# Cameras.net
KiCad netlist of a schematic drawn in Altium Designer
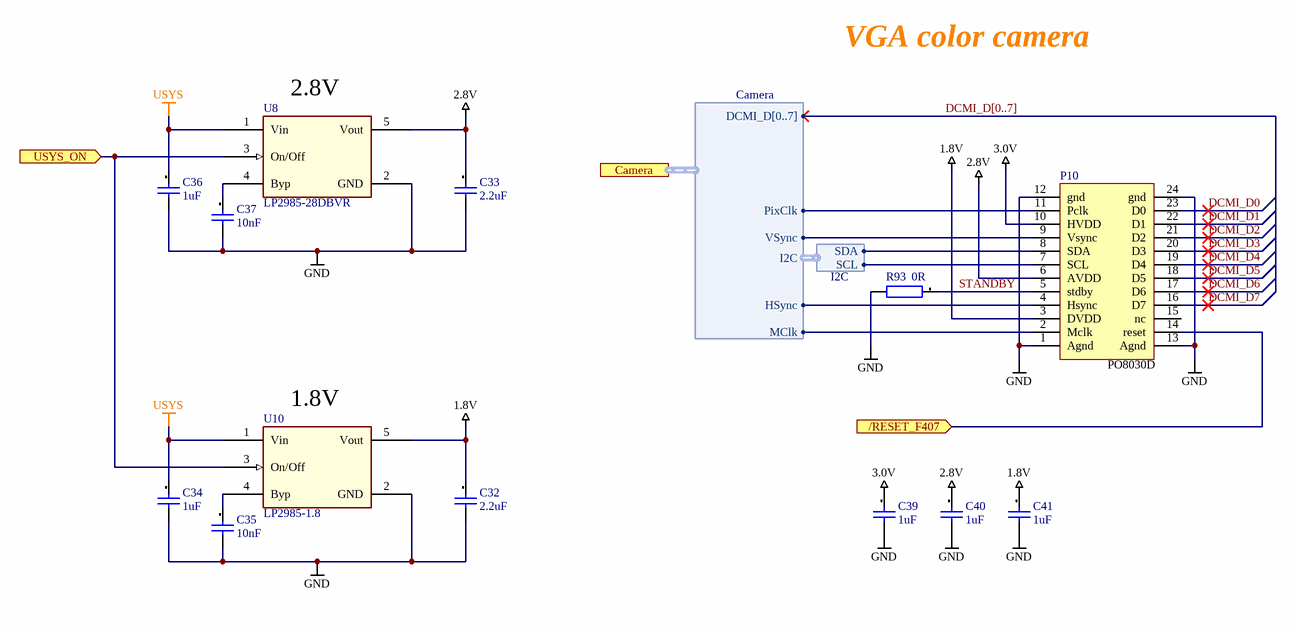
[diagram p0: Cameras.SchDoc]

(export (version "E")
  (design (tool "Eeschema 10.0.6"))
  (components
    (comp (ref "C32")
      (value "2.2uF")
      (footprint "ROB_0603")
      (description "Capacitor")
      (fields (field (name "MANUFACTURER") "Kemet") (field (name "VOLTAGE") "10"))
      (libsource (lib "LSRO1Altium") (part "CAP-NP"))
    )
    (comp (ref "C33")
      (value "2.2uF")
      (footprint "ROB_0603")
      (description "Capacitor")
      (fields (field (name "MANUFACTURER") "Kemet") (field (name "VOLTAGE") "10"))
      (libsource (lib "LSRO1Altium") (part "CAP-NP"))
    )
    (comp (ref "C34")
      (value "1uF")
      (footprint "ROB_0603")
      (description "Capacitor")
      (fields (field (name "MANUFACTURER") "Kemet") (field (name "VOLTAGE") "25"))
      (libsource (lib "LSRO1Altium") (part "CAP-NP"))
    )
    (comp (ref "C35")
      (value "10nF")
      (footprint "ROB_0603")
      (description "Capacitor")
      (fields (field (name "MANUFACTURER") "Multicomp") (field (name "VOLTAGE") "50"))
      (libsource (lib "LSRO1Altium") (part "CAP-NP"))
    )
    (comp (ref "C36")
      (value "1uF")
      (footprint "ROB_0603")
      (description "Capacitor")
      (fields (field (name "MANUFACTURER") "Kemet") (field (name "VOLTAGE") "25"))
      (libsource (lib "LSRO1Altium") (part "CAP-NP"))
    )
    (comp (ref "C37")
      (value "10nF")
      (footprint "ROB_0603")
      (description "Capacitor")
      (fields (field (name "MANUFACTURER") "Multicomp") (field (name "VOLTAGE") "50"))
      (libsource (lib "LSRO1Altium") (part "CAP-NP"))
    )
    (comp (ref "C39")
      (value "1uF")
      (footprint "ROB_0603")
      (description "Capacitor")
      (fields (field (name "MANUFACTURER") "Kemet") (field (name "VOLTAGE") "25"))
      (libsource (lib "LSRO1Altium") (part "CAP-NP"))
    )
    (comp (ref "C40")
      (value "1uF")
      (footprint "ROB_0603")
      (description "Capacitor")
      (fields (field (name "MANUFACTURER") "Kemet") (field (name "VOLTAGE") "25"))
      (libsource (lib "LSRO1Altium") (part "CAP-NP"))
    )
    (comp (ref "C41")
      (value "1uF")
      (footprint "ROB_0603")
      (description "Capacitor")
      (fields (field (name "MANUFACTURER") "Kemet") (field (name "VOLTAGE") "25"))
      (libsource (lib "LSRO1Altium") (part "CAP-NP"))
    )
    (comp (ref "P10")
      (value "24-5805-024-000-829")
      (footprint "Connector 24-5805-024-000-829")
      (description "RCPT 24 pins camera 24-5805-024-000-829")
      (libsource (lib "Dev_Card_Lib") (part "24-5805-024-000-829"))
    )
    (comp (ref "R93")
      (value "0R")
      (footprint "ROB_0603")
      (description "Resistor")
      (fields (field (name "TOLERANCE") "+/-1") (field (name "MANUFACTURER") "Multicomp"))
      (libsource (lib "LSRO1Altium") (part "RES"))
    )
    (comp (ref "U8")
      (value "LP2985-28DBVR")
      (footprint "SOT95P285X100-5L")
      (description "IC REG LDO 2.8V 0.15A SOT23-5")
      (fields (field (name "MANUFACTURER") "Texas Instruments") (field (name "Comment") "LDO 2V8"))
      (libsource (lib "Dev_Card_Lib") (part "LP2985-28DBVR"))
    )
    (comp (ref "U10")
      (value "LP2985-1.8")
      (footprint "SOT95P285X100-5L")
      (description "LDO 1.8V, 150mA, SOT23-5")
      (fields (field (name "MANUFACTURER") "National") (field (name "Comment") "LDO 1V8"))
      (libsource (lib "LSRO1Altium") (part "S-LP2985IM5"))
    )
  )
  (nets
    (net (code "12") (name "/DCMI_D0") (class "Default")
      (node (ref "P10") (pin "23") (pinfunction "D0_23") (pintype "passive"))
    )
    (net (code "13") (name "/DCMI_D1") (class "Default")
      (node (ref "P10") (pin "22") (pinfunction "D1_22") (pintype "passive"))
    )
    (net (code "14") (name "/DCMI_D2") (class "Default")
      (node (ref "P10") (pin "21") (pinfunction "D2_21") (pintype "passive"))
    )
    (net (code "15") (name "/DCMI_D3") (class "Default")
      (node (ref "P10") (pin "20") (pinfunction "D3_20") (pintype "passive"))
    )
    (net (code "16") (name "/DCMI_D4") (class "Default")
      (node (ref "P10") (pin "19") (pinfunction "D4_19") (pintype "passive"))
    )
    (net (code "17") (name "/DCMI_D5") (class "Default")
      (node (ref "P10") (pin "18") (pinfunction "D5_18") (pintype "passive"))
    )
    (net (code "18") (name "/DCMI_D6") (class "Default")
      (node (ref "P10") (pin "17") (pinfunction "D6_17") (pintype "passive"))
    )
    (net (code "19") (name "/DCMI_D7") (class "Default")
      (node (ref "P10") (pin "16") (pinfunction "D7_16") (pintype "passive"))
    )
    (net (code "22") (name "/HSync") (class "Default")
      (node (ref "P10") (pin "4") (pinfunction "Hsync_4") (pintype "passive"))
    )
    (net (code "23") (name "/MClk") (class "Default")
      (node (ref "P10") (pin "2") (pinfunction "Mclk_2") (pintype "passive"))
    )
    (net (code "24") (name "/PixClk") (class "Default")
      (node (ref "P10") (pin "11") (pinfunction "Pclk_11") (pintype "passive"))
    )
    (net (code "25") (name "/SCL") (class "Default")
      (node (ref "P10") (pin "7") (pinfunction "SCL_7") (pintype "passive"))
    )
    (net (code "26") (name "/SDA") (class "Default")
      (node (ref "P10") (pin "8") (pinfunction "SDA_8") (pintype "passive"))
    )
    (net (code "27") (name "/STANDBY") (class "Default")
      (node (ref "P10") (pin "5") (pinfunction "stdby_5") (pintype "passive"))
      (node (ref "R93") (pin "1") (pinfunction "1_1") (pintype "passive"))
    )
    (net (code "28") (name "/USYS_ON") (class "Default")
      (node (ref "U10") (pin "3") (pinfunction "On/Off_3") (pintype "input"))
      (node (ref "U8") (pin "3") (pinfunction "On/Off_3") (pintype "input"))
    )
    (net (code "29") (name "/VSync") (class "Default")
      (node (ref "P10") (pin "9") (pinfunction "Vsync_9") (pintype "passive"))
    )
    (net (code "30") (name "/{slash}RESET_F407") (class "Default")
      (node (ref "P10") (pin "14") (pinfunction "reset_14") (pintype "passive"))
    )
    (net (code "31") (name "1.8V") (class "Default")
      (node (ref "C32") (pin "1") (pinfunction "1_1") (pintype "passive"))
      (node (ref "C41") (pin "1") (pinfunction "1_1") (pintype "passive"))
      (node (ref "P10") (pin "3") (pinfunction "DVDD_3") (pintype "passive"))
      (node (ref "U10") (pin "5") (pinfunction "Vout_5") (pintype "power_in"))
    )
    (net (code "32") (name "2.8V") (class "Default")
      (node (ref "C33") (pin "1") (pinfunction "1_1") (pintype "passive"))
      (node (ref "C40") (pin "1") (pinfunction "1_1") (pintype "passive"))
      (node (ref "P10") (pin "6") (pinfunction "AVDD_6") (pintype "passive"))
      (node (ref "U8") (pin "5") (pinfunction "Vout_5") (pintype "power_in"))
    )
    (net (code "33") (name "3.0V") (class "Default")
      (node (ref "C39") (pin "1") (pinfunction "1_1") (pintype "passive"))
      (node (ref "P10") (pin "10") (pinfunction "HVDD_10") (pintype "passive"))
    )
    (net (code "34") (name "GND") (class "Default")
      (node (ref "C32") (pin "2") (pinfunction "2_2") (pintype "passive"))
      (node (ref "C33") (pin "2") (pinfunction "2_2") (pintype "passive"))
      (node (ref "C34") (pin "2") (pinfunction "2_2") (pintype "passive"))
      (node (ref "C35") (pin "2") (pinfunction "2_2") (pintype "passive"))
      (node (ref "C36") (pin "2") (pinfunction "2_2") (pintype "passive"))
      (node (ref "C37") (pin "2") (pinfunction "2_2") (pintype "passive"))
      (node (ref "C39") (pin "2") (pinfunction "2_2") (pintype "passive"))
      (node (ref "C40") (pin "2") (pinfunction "2_2") (pintype "passive"))
      (node (ref "C41") (pin "2") (pinfunction "2_2") (pintype "passive"))
      (node (ref "P10") (pin "1") (pinfunction "Agnd_1") (pintype "passive"))
      (node (ref "P10") (pin "12") (pinfunction "gnd_12") (pintype "passive"))
      (node (ref "P10") (pin "13") (pinfunction "Agnd_13") (pintype "passive"))
      (node (ref "P10") (pin "24") (pinfunction "gnd_24") (pintype "passive"))
      (node (ref "R93") (pin "2") (pinfunction "2_2") (pintype "passive"))
      (node (ref "U10") (pin "2") (pinfunction "GND_2") (pintype "power_in"))
      (node (ref "U8") (pin "2") (pinfunction "GND_2") (pintype "power_in"))
    )
    (net (code "35") (name "Net-(U8-Byp)") (class "Default")
      (node (ref "C37") (pin "1") (pinfunction "1_1") (pintype "passive"))
      (node (ref "U8") (pin "4") (pinfunction "Byp_4") (pintype "passive"))
    )
    (net (code "36") (name "Net-(U10-Byp)") (class "Default")
      (node (ref "C35") (pin "1") (pinfunction "1_1") (pintype "passive"))
      (node (ref "U10") (pin "4") (pinfunction "Byp_4") (pintype "passive"))
    )
    (net (code "37") (name "USYS") (class "Default")
      (node (ref "C34") (pin "1") (pinfunction "1_1") (pintype "passive"))
      (node (ref "C36") (pin "1") (pinfunction "1_1") (pintype "passive"))
      (node (ref "U10") (pin "1") (pinfunction "Vin_1") (pintype "power_in"))
      (node (ref "U8") (pin "1") (pinfunction "Vin_1") (pintype "power_in"))
    )
    (net (code "38") (name "unconnected-(P10-nc-Pad15)") (class "Default")
      (node (ref "P10") (pin "15") (pinfunction "nc_15") (pintype "passive"))
    )
  )
)
